# led_driver_1.net
KiCad netlist of a schematic drawn in EAGLE
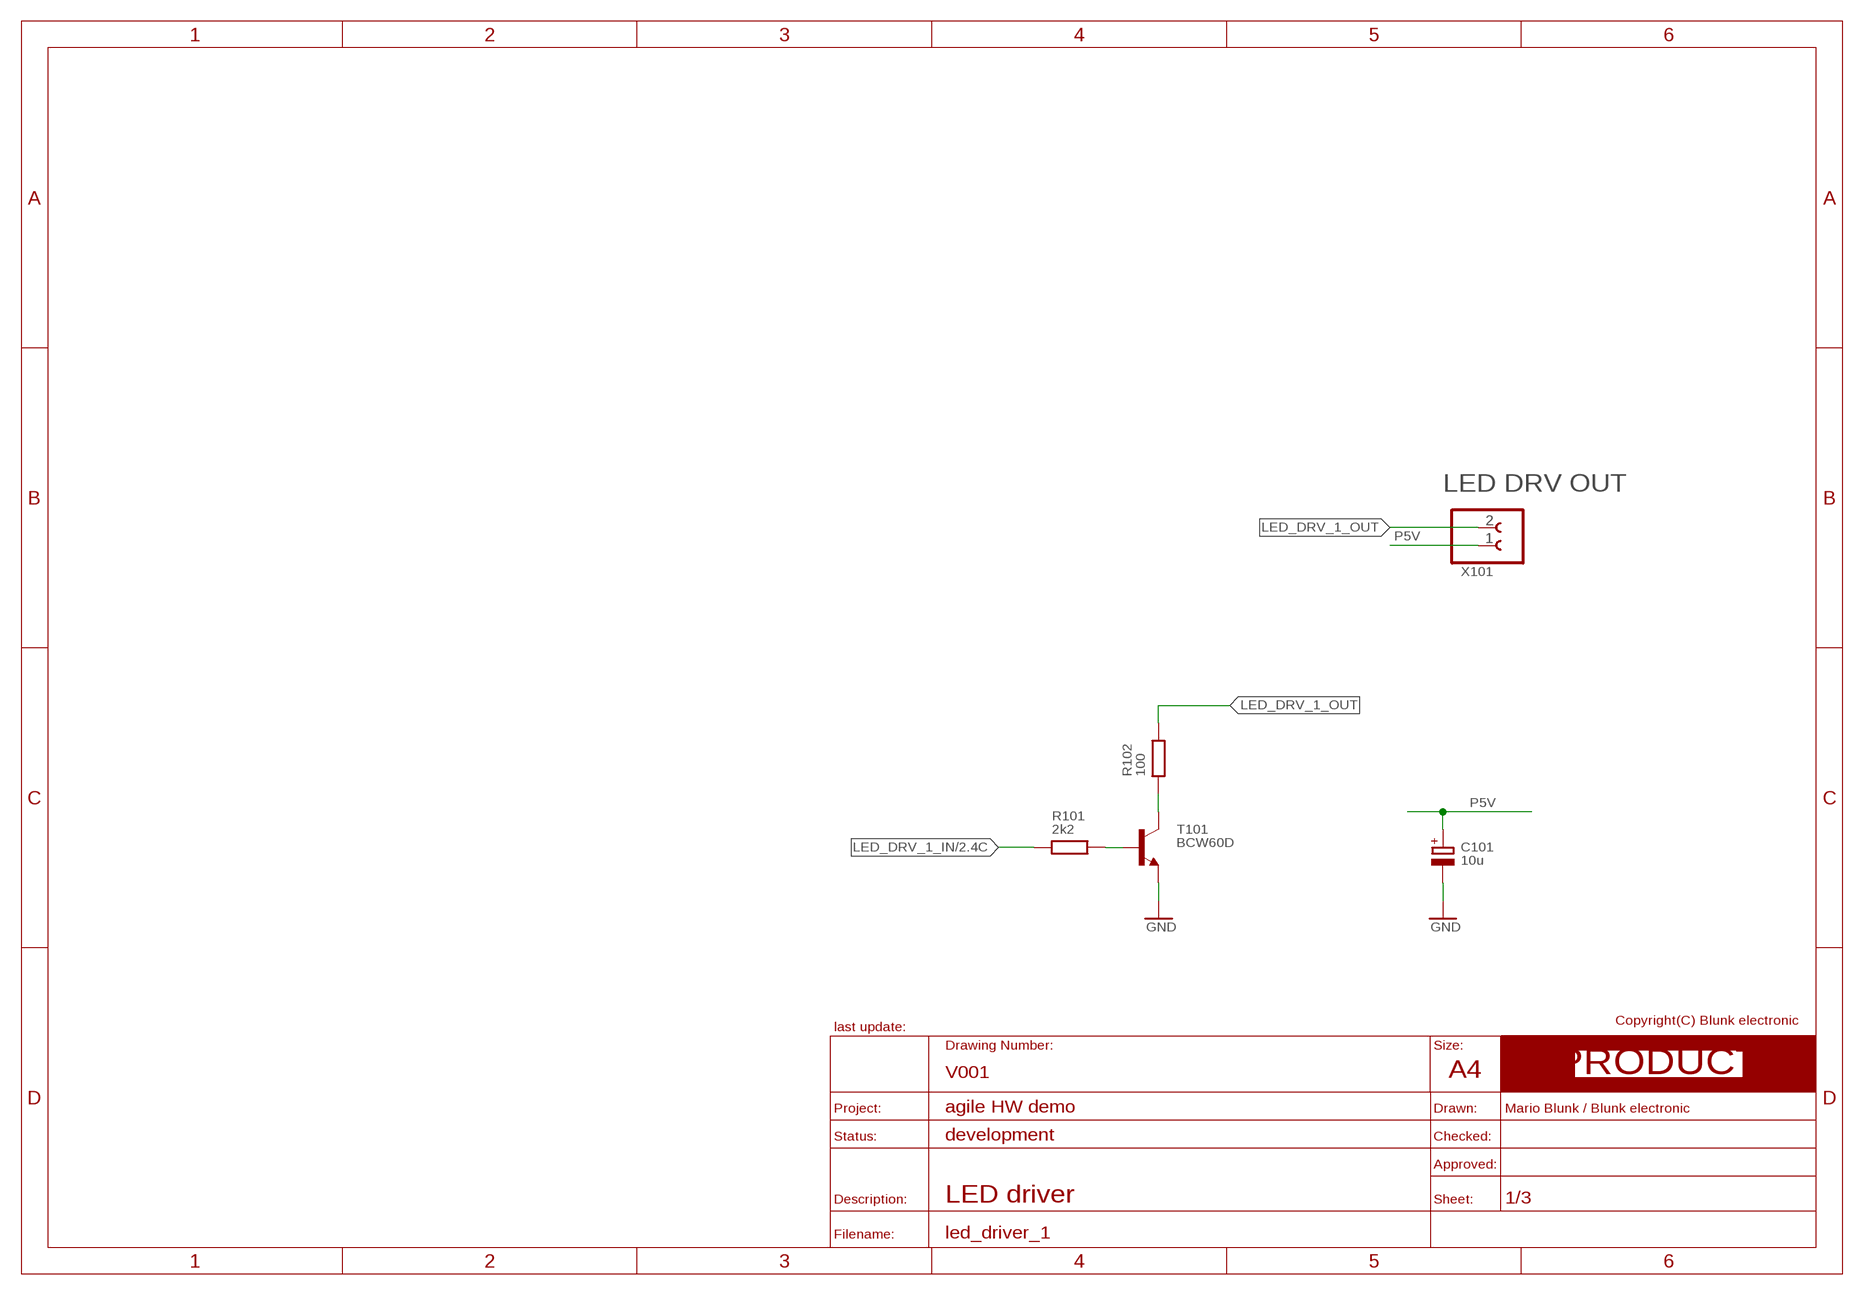
[diagram p0: schematic, sheet 1]
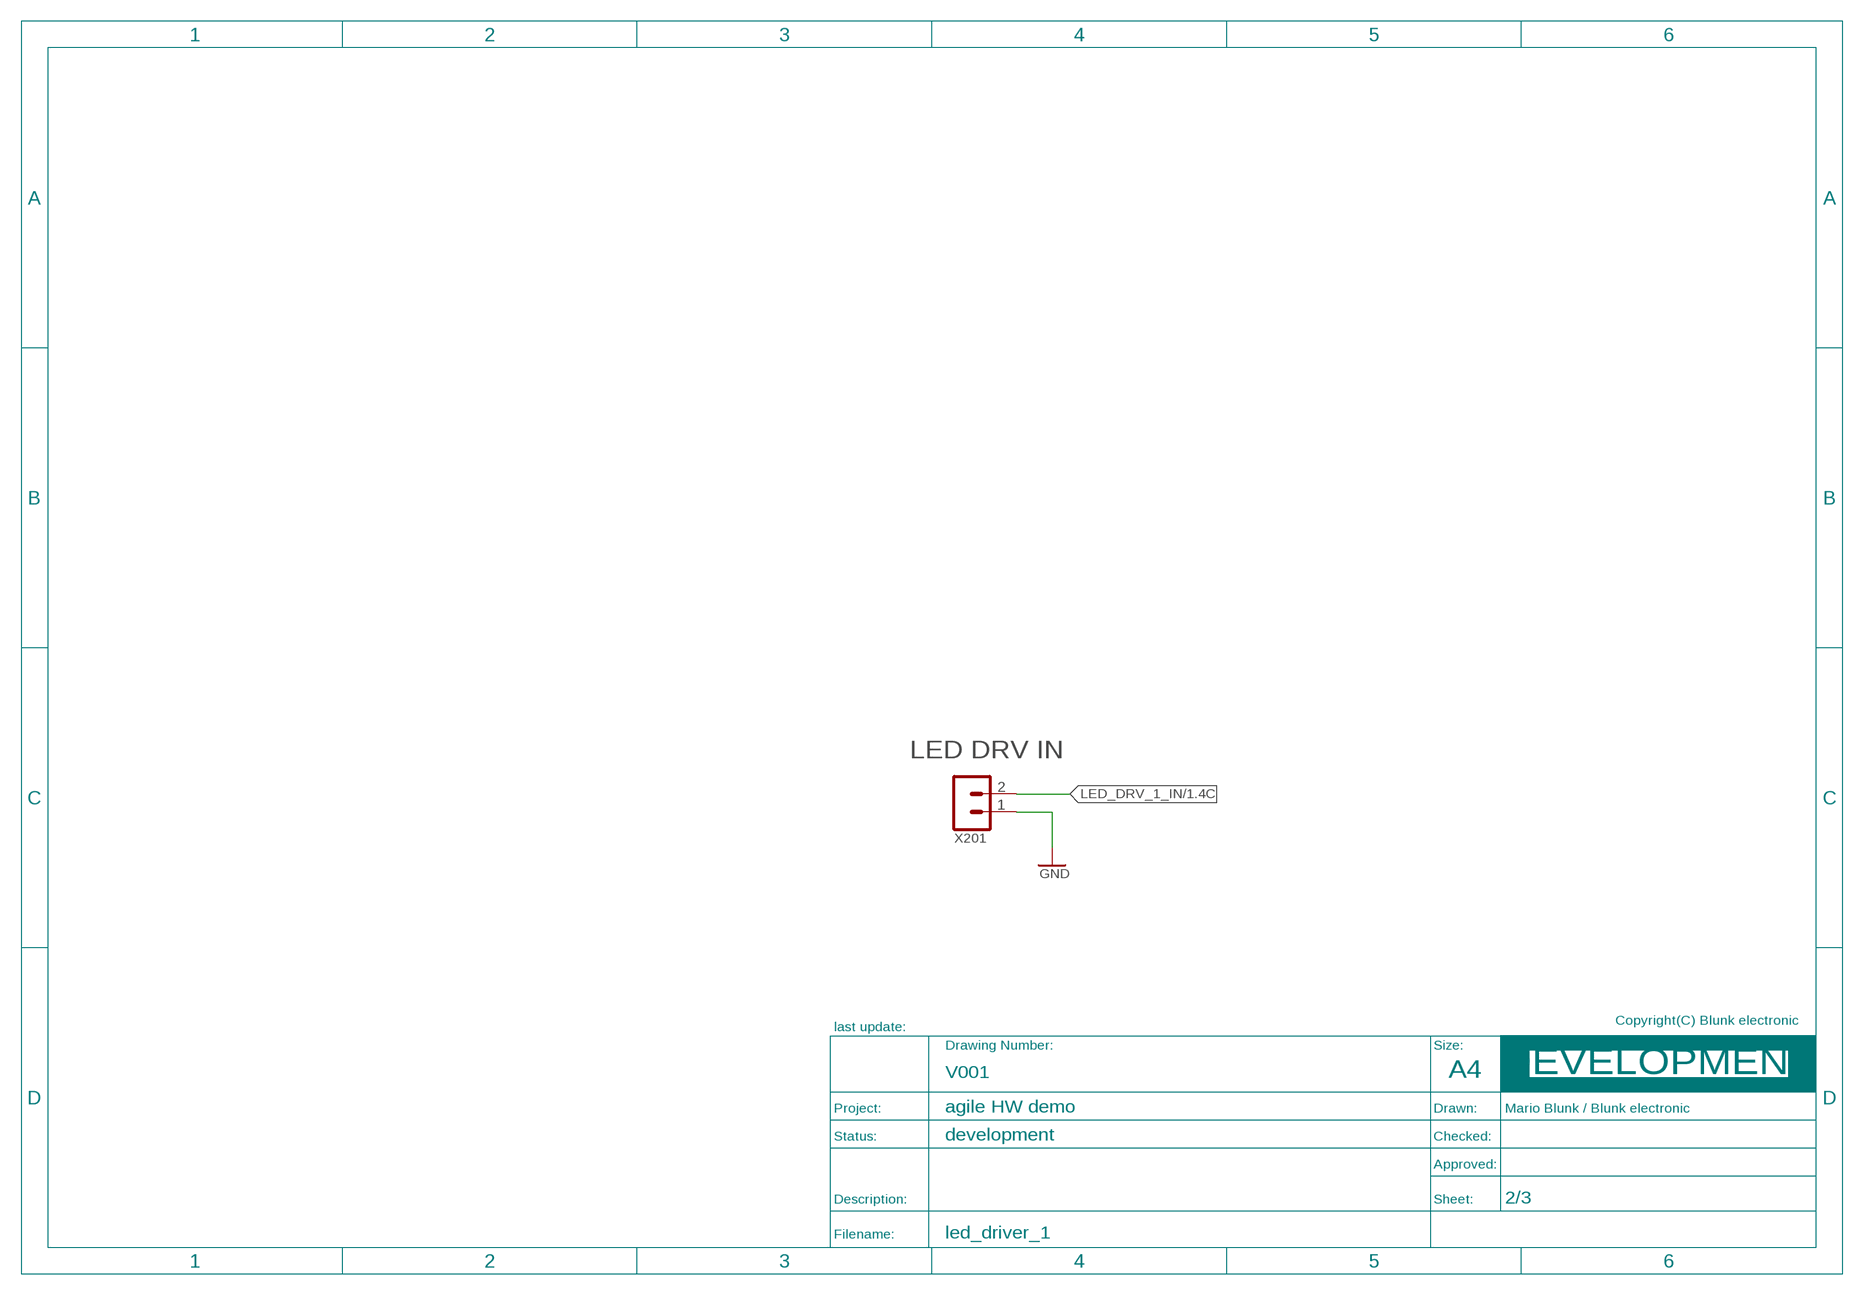
[diagram p1: schematic, sheet 2]
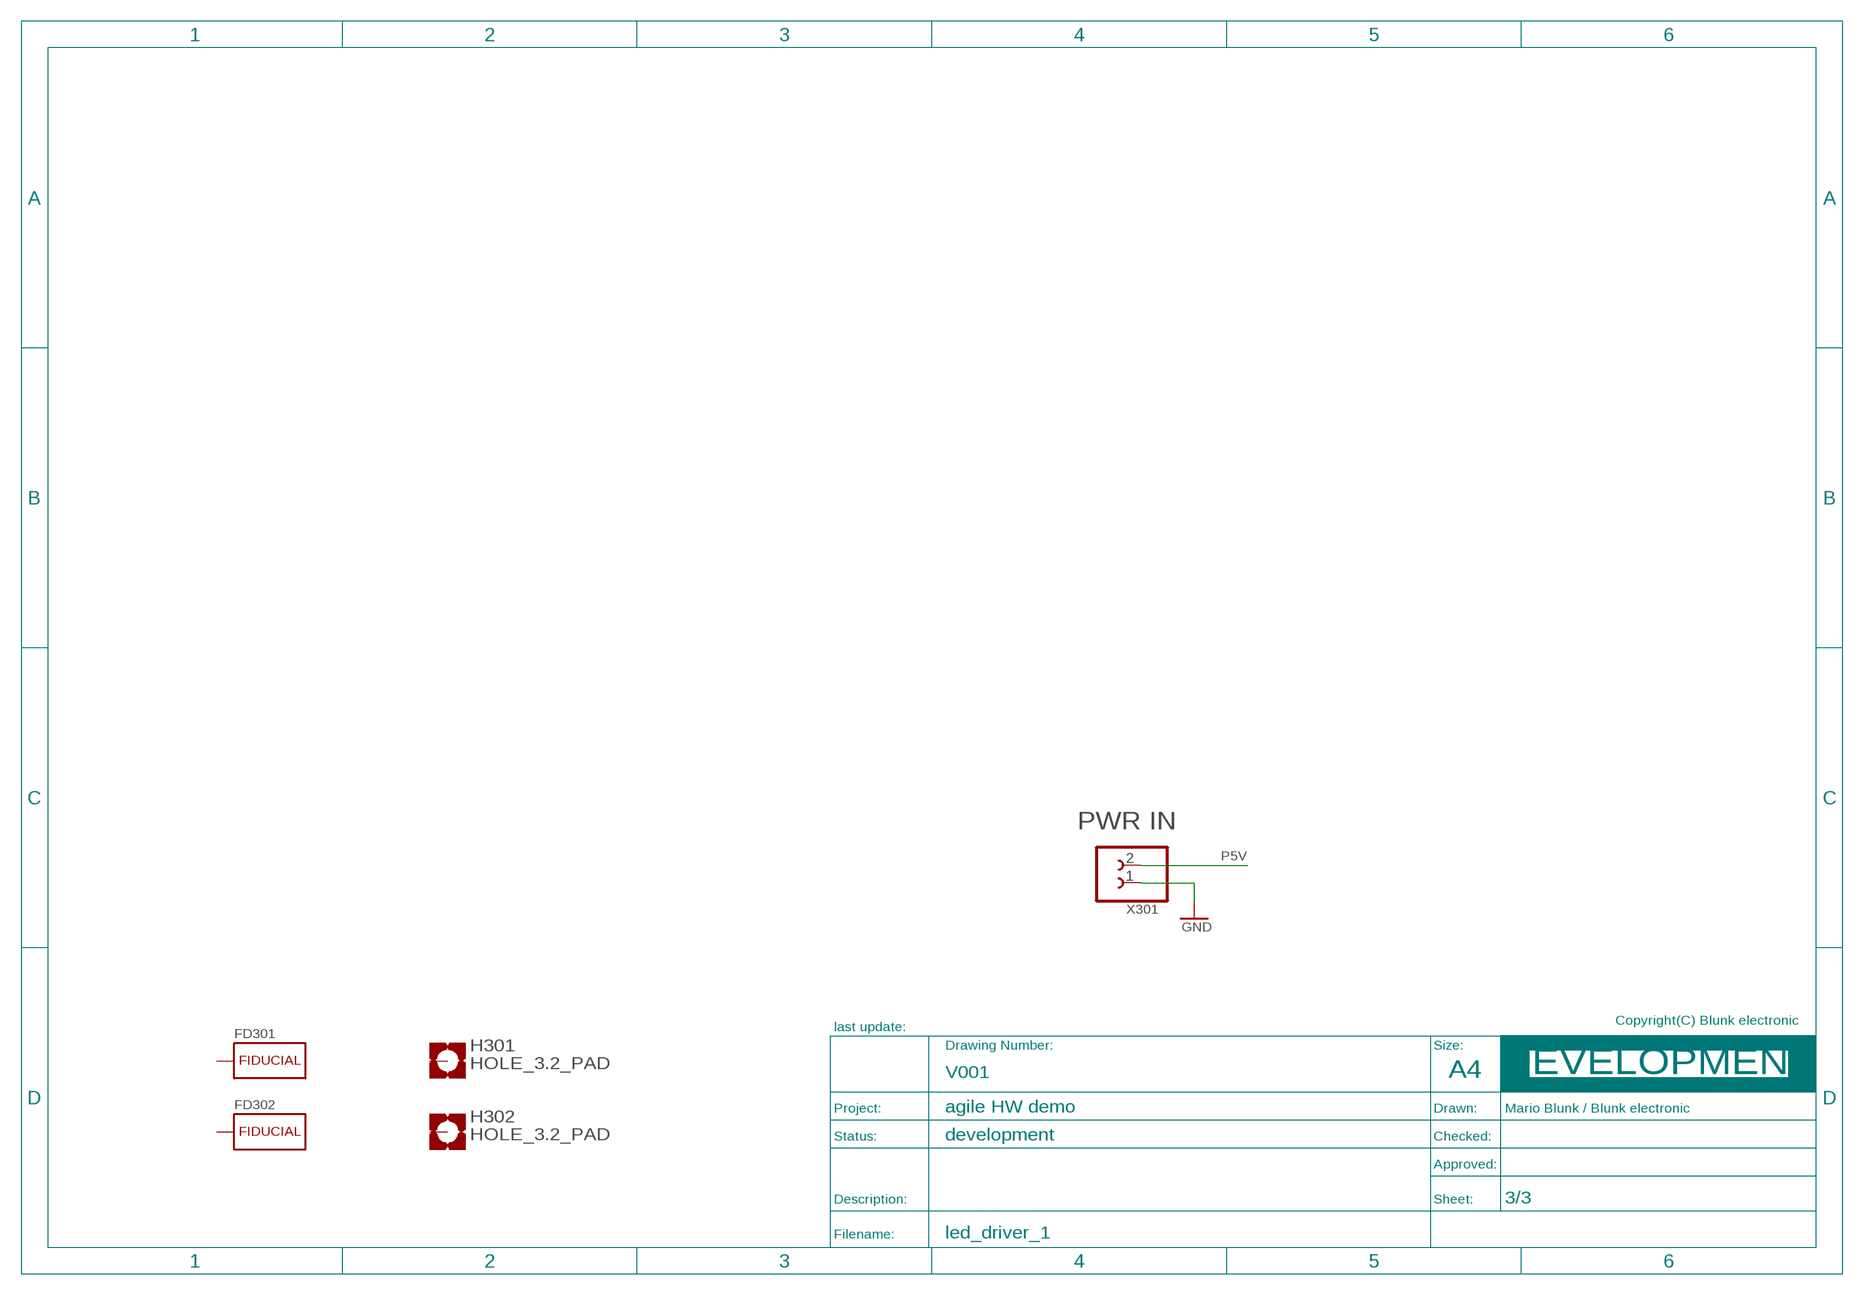
[diagram p2: schematic, sheet 3]

(export (version "E")
  (design (tool "Eeschema 10.0.6"))
  (components
    (comp (ref "X201")
      (value "MALE_2X1-T-VERTICAL")
      (footprint "eagle-import:T_MALE_2X1_VERTICAL_PITCH_2MM54")
      (fields (field (name "FUNCTION") "LED DRV IN"))
      (libsource (lib "eagle-import") (part "MALE_2X1-T-VERTICAL"))
    )
    (comp (ref "FD301")
      (value "FIDUCIAL_CROSSHAIR")
      (footprint "eagle-import:CROSSHAIR")
      (libsource (lib "eagle-import") (part "FIDUCIAL_CROSSHAIR"))
    )
    (comp (ref "FD302")
      (value "FIDUCIAL_CROSSHAIR")
      (footprint "eagle-import:CROSSHAIR")
      (libsource (lib "eagle-import") (part "FIDUCIAL_CROSSHAIR"))
    )
    (comp (ref "H301")
      (value "HOLE_3.2_PAD")
      (footprint "eagle-import:3.2_PAD")
      (libsource (lib "eagle-import") (part "HOLE_3.2_PAD"))
    )
    (comp (ref "H302")
      (value "HOLE_3.2_PAD")
      (footprint "eagle-import:3.2_PAD")
      (libsource (lib "eagle-import") (part "HOLE_3.2_PAD"))
    )
    (comp (ref "X301")
      (value "CLAMP_1X2-T-2.5MM")
      (footprint "eagle-import:T_WIRE_CLAMP_1X2_PITCH_2MM5")
      (fields (field (name "FUNCTION") "PWR IN"))
      (libsource (lib "eagle-import") (part "CLAMP_1X2-T-2.5MM"))
    )
    (comp (ref "C101")
      (value "10u")
      (footprint "eagle-import:S_6032")
      (fields (field (name "PART_CODE_BEL") "C_PAC_S_6032_VAL_10u_Vmax_35V"))
      (libsource (lib "eagle-import") (part "C_POL_S_6032"))
    )
    (comp (ref "R101")
      (value "2k2")
      (footprint "eagle-import:S_0805")
      (fields (field (name "PART_CODE_BEL") "R_PAC_S_0805_VAL_2k2"))
      (libsource (lib "eagle-import") (part "R_S_0805"))
    )
    (comp (ref "R102")
      (value "100")
      (footprint "eagle-import:S_0805")
      (fields (field (name "PART_CODE_BEL") "R_PAC_S_0805_VAL_100"))
      (libsource (lib "eagle-import") (part "R_S_0805"))
    )
    (comp (ref "T101")
      (value "BCW60D")
      (footprint "eagle-import:S_SOT23")
      (fields (field (name "PART_CODE_BEL") "T_PAC_S_SOT23_VAL_BCW60D"))
      (libsource (lib "eagle-import") (part "NPN_S_SOT23"))
    )
    (comp (ref "X101")
      (value "CLAMP_1X2-T-2.5MM")
      (footprint "eagle-import:T_WIRE_CLAMP_1X2_PITCH_2MM5")
      (fields (field (name "FUNCTION") "LED DRV OUT"))
      (libsource (lib "eagle-import") (part "CLAMP_1X2-T-2.5MM"))
    )
  )
  (nets
    (net (code "1") (name "GND") (class "Default")
      (node (ref "C101") (pin "-") (pinfunction "-_-") (pintype "passive"))
      (node (ref "T101") (pin "2") (pinfunction "E_2") (pintype "passive"))
      (node (ref "X201") (pin "1") (pinfunction "1_1") (pintype "passive"))
      (node (ref "X301") (pin "1") (pinfunction "1_1") (pintype "passive"))
    )
    (net (code "2") (name "LED_DRV_1_IN") (class "Default")
      (node (ref "R101") (pin "1") (pinfunction "1_1") (pintype "passive"))
      (node (ref "X201") (pin "2") (pinfunction "2_2") (pintype "passive"))
    )
    (net (code "3") (name "LED_DRV_1_OUT") (class "Default")
      (node (ref "R102") (pin "2") (pinfunction "2_2") (pintype "passive"))
      (node (ref "X101") (pin "2") (pinfunction "2_2") (pintype "passive"))
    )
    (net (code "4") (name "Net-(T101-B)") (class "Default")
      (node (ref "R101") (pin "2") (pinfunction "2_2") (pintype "passive"))
      (node (ref "T101") (pin "1") (pinfunction "B_1") (pintype "passive"))
    )
    (net (code "5") (name "Net-(T101-C)") (class "Default")
      (node (ref "R102") (pin "1") (pinfunction "1_1") (pintype "passive"))
      (node (ref "T101") (pin "3") (pinfunction "C_3") (pintype "passive"))
    )
    (net (code "6") (name "P5V") (class "Default")
      (node (ref "C101") (pin "+") (pinfunction "+_+") (pintype "passive"))
      (node (ref "X101") (pin "1") (pinfunction "1_1") (pintype "passive"))
      (node (ref "X301") (pin "2") (pinfunction "2_2") (pintype "passive"))
    )
    (net (code "7") (name "unconnected-(FD301-NC-Pad1)") (class "Default")
      (node (ref "FD301") (pin "1") (pinfunction "NC_1") (pintype "no_connect"))
    )
    (net (code "8") (name "unconnected-(FD302-NC-Pad1)") (class "Default")
      (node (ref "FD302") (pin "1") (pinfunction "NC_1") (pintype "no_connect"))
    )
    (net (code "9") (name "unconnected-(H301-MOUNT-PadH1)") (class "Default")
      (node (ref "H301") (pin "H1") (pinfunction "MOUNT_H1") (pintype "passive"))
    )
    (net (code "10") (name "unconnected-(H302-MOUNT-PadH1)") (class "Default")
      (node (ref "H302") (pin "H1") (pinfunction "MOUNT_H1") (pintype "passive"))
    )
  )
)
